# esp32.net
KiCad netlist of a schematic drawn in Altium Designer
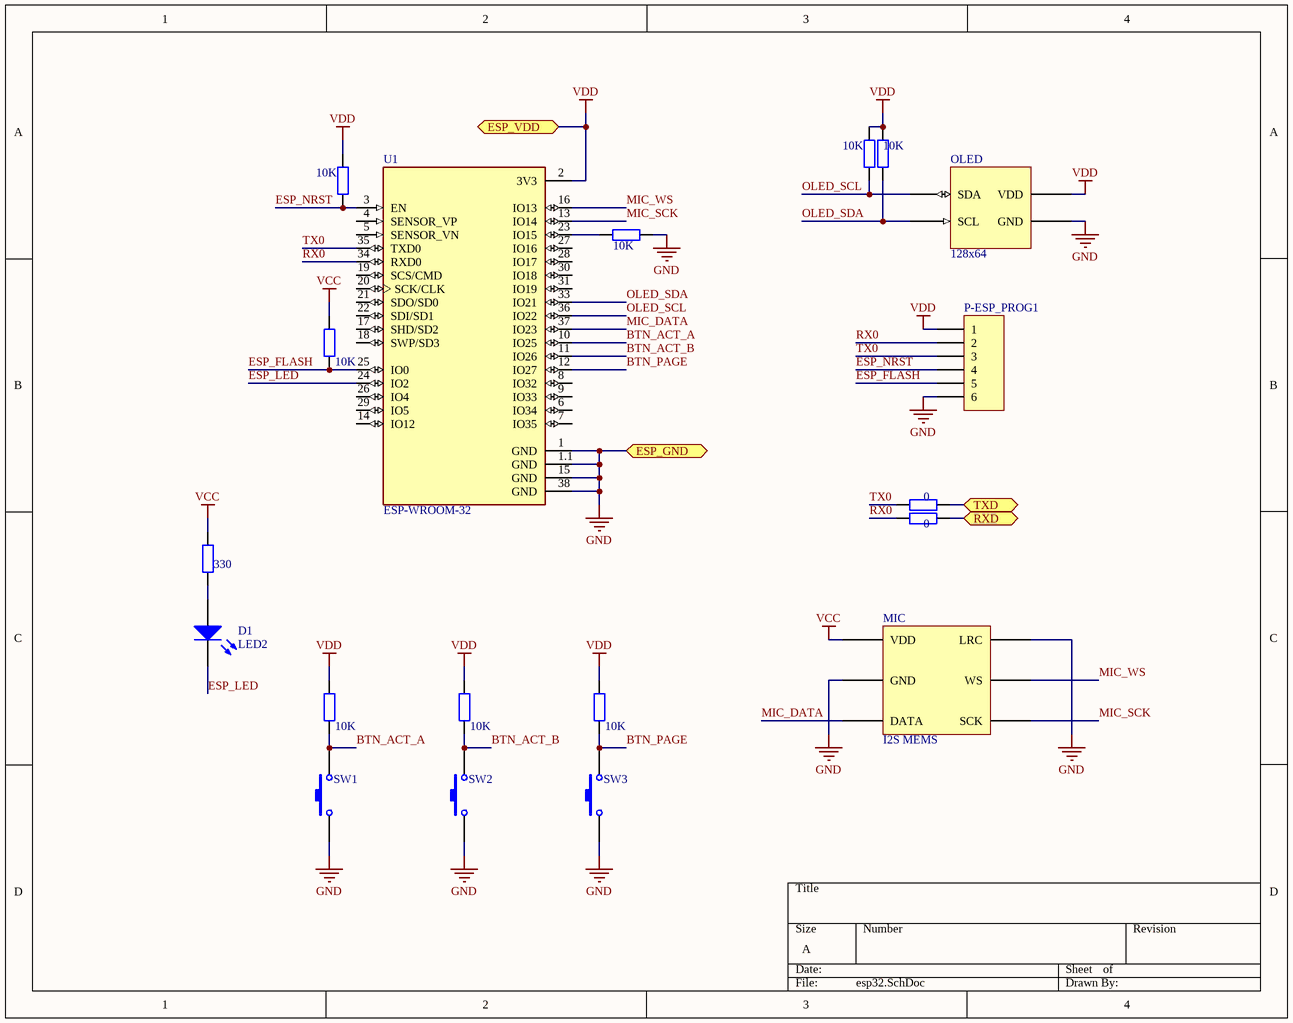
[diagram p0: esp32.SchDoc]

(export (version "E")
  (design (tool "Eeschema 10.0.6"))
  (components
    (comp (ref "D1")
      (value "LED2")
      (footprint "3.2X1.6X1.1")
      (description "Typical RED, GREEN, YELLOW, AMBER GaAs LED")
      (fields (field (name "PUBLISHER") "Altium Limited"))
      (libsource (lib "Miscellaneous Devices") (part "LED2"))
    )
    (comp (ref "MIC") (value "I2S MEMS") (libsource (lib "INMP441") (part "INMP441")))
    (comp (ref "OLED") (value "128x64") (libsource (lib "SH1106") (part "SH1106")))
    (comp (ref "P-ESP_PROG1")
      (value "Header 6")
      (footprint "HDR1X6")
      (description "Header, 6-Pin")
      (fields (field (name "PUBLISHER") "Altium Limited"))
      (libsource (lib "Miscellaneous Connectors") (part "Header 6"))
    )
    (comp (ref "R-BUTTON1")
      (value "10K")
      (footprint "AXIAL-0.4")
      (description "Resistor")
      (fields (field (name "Comment") "Res2") (field (name "PUBLISHER") "Altium Limited"))
      (libsource (lib "Miscellaneous Devices") (part "Res2"))
    )
    (comp (ref "R-BUTTON2")
      (value "10K")
      (footprint "AXIAL-0.4")
      (description "Resistor")
      (fields (field (name "Comment") "Res2") (field (name "PUBLISHER") "Altium Limited"))
      (libsource (lib "Miscellaneous Devices") (part "Res2"))
    )
    (comp (ref "R-BUTTON3")
      (value "10K")
      (footprint "AXIAL-0.4")
      (description "Resistor")
      (fields (field (name "Comment") "Res2") (field (name "PUBLISHER") "Altium Limited"))
      (libsource (lib "Miscellaneous Devices") (part "Res2"))
    )
    (comp (ref "R-ESP-LOG1")
      (value "10K")
      (footprint "AXIAL-0.4")
      (description "Resistor")
      (fields (field (name "Comment") "Res2") (field (name "PUBLISHER") "Altium Limited"))
      (libsource (lib "") (part "Res2_2"))
    )
    (comp (ref "R-ESP1")
      (value "10K")
      (footprint "AXIAL-0.4")
      (description "Resistor")
      (fields (field (name "Comment") "Res2") (field (name "PUBLISHER") "Altium Limited"))
      (libsource (lib "Miscellaneous Devices") (part "Res2"))
    )
    (comp (ref "R-ESP2")
      (value "10K")
      (footprint "AXIAL-0.4")
      (description "Resistor")
      (fields (field (name "Comment") "Res2") (field (name "PUBLISHER") "Altium Limited"))
      (libsource (lib "Miscellaneous Devices") (part "Res2"))
    )
    (comp (ref "R-LED1")
      (value "330")
      (footprint "AXIAL-0.4")
      (description "Resistor")
      (fields (field (name "Comment") "Res2") (field (name "PUBLISHER") "Altium Limited"))
      (libsource (lib "Miscellaneous Devices") (part "Res2"))
    )
    (comp (ref "R-OLED1")
      (value "10K")
      (footprint "AXIAL-0.4")
      (description "Resistor")
      (fields (field (name "Comment") "Res2") (field (name "PUBLISHER") "Altium Limited"))
      (libsource (lib "Miscellaneous Devices") (part "Res2"))
    )
    (comp (ref "R-OLED2")
      (value "10K")
      (footprint "AXIAL-0.4")
      (description "Resistor")
      (fields (field (name "Comment") "Res2") (field (name "PUBLISHER") "Altium Limited"))
      (libsource (lib "Miscellaneous Devices") (part "Res2"))
    )
    (comp (ref "R-UART1")
      (value "0")
      (footprint "AXIAL-0.4")
      (description "Resistor")
      (fields (field (name "Comment") "Res2") (field (name "PUBLISHER") "Altium Limited"))
      (libsource (lib "") (part "Res2_1"))
    )
    (comp (ref "R-UART2")
      (value "0")
      (footprint "AXIAL-0.4")
      (description "Resistor")
      (fields (field (name "Comment") "Res2") (field (name "PUBLISHER") "Altium Limited"))
      (libsource (lib "") (part "Res2_1"))
    )
    (comp (ref "SW1")
      (value "SW-PB")
      (footprint "SPST-2")
      (description "Switch")
      (fields (field (name "PUBLISHER") "Altium Limited"))
      (libsource (lib "Miscellaneous Devices") (part "SW-PB"))
    )
    (comp (ref "SW2")
      (value "SW-PB")
      (footprint "SPST-2")
      (description "Switch")
      (fields (field (name "PUBLISHER") "Altium Limited"))
      (libsource (lib "Miscellaneous Devices") (part "SW-PB"))
    )
    (comp (ref "SW3")
      (value "SW-PB")
      (footprint "SPST-2")
      (description "Switch")
      (fields (field (name "PUBLISHER") "Altium Limited"))
      (libsource (lib "Miscellaneous Devices") (part "SW-PB"))
    )
    (comp (ref "U1")
      (value "ESP-WROOM-32")
      (footprint "MODULE_ESP-WROOM-32")
      (description "WiFi 802.11b/g/n/d/e/i Transceiver Module 2.4GHz Surface Mount")
      (fields (field (name "MF") "Olimex LTD"))
      (libsource (lib "ESP-WROOM-32") (part "ESP-WROOM-32"))
    )
  )
  (nets
    (net (code "1") (name "/BTN_ACT_A") (class "Default")
      (node (ref "R-BUTTON1") (pin "1") (pinfunction "1_1") (pintype "passive"))
      (node (ref "SW1") (pin "2") (pinfunction "2_2") (pintype "passive"))
      (node (ref "U1") (pin "10") (pinfunction "IO25_10") (pintype "bidirectional"))
    )
    (net (code "2") (name "/BTN_ACT_B") (class "Default")
      (node (ref "R-BUTTON2") (pin "1") (pinfunction "1_1") (pintype "passive"))
      (node (ref "SW2") (pin "2") (pinfunction "2_2") (pintype "passive"))
      (node (ref "U1") (pin "11") (pinfunction "IO26_11") (pintype "bidirectional"))
    )
    (net (code "3") (name "/BTN_PAGE") (class "Default")
      (node (ref "R-BUTTON3") (pin "1") (pinfunction "1_1") (pintype "passive"))
      (node (ref "SW3") (pin "2") (pinfunction "2_2") (pintype "passive"))
      (node (ref "U1") (pin "12") (pinfunction "IO27_12") (pintype "bidirectional"))
    )
    (net (code "4") (name "/ESP_FLASH") (class "Default")
      (node (ref "P-ESP_PROG1") (pin "5") (pinfunction "5_5") (pintype "passive"))
      (node (ref "R-ESP2") (pin "1") (pinfunction "1_1") (pintype "passive"))
      (node (ref "U1") (pin "25") (pinfunction "IO0_25") (pintype "bidirectional"))
    )
    (net (code "5") (name "/ESP_LED") (class "Default")
      (node (ref "D1") (pin "2") (pinfunction "K_2") (pintype "passive"))
      (node (ref "U1") (pin "24") (pinfunction "IO2_24") (pintype "bidirectional"))
    )
    (net (code "6") (name "/ESP_NRST") (class "Default")
      (node (ref "P-ESP_PROG1") (pin "4") (pinfunction "4_4") (pintype "passive"))
      (node (ref "R-ESP1") (pin "1") (pinfunction "1_1") (pintype "passive"))
      (node (ref "U1") (pin "3") (pinfunction "EN_3") (pintype "input"))
    )
    (net (code "7") (name "/MIC_DATA") (class "Default")
      (node (ref "MIC") (pin "DATA") (pinfunction "DATA_DATA") (pintype "passive"))
      (node (ref "U1") (pin "37") (pinfunction "IO23_37") (pintype "bidirectional"))
    )
    (net (code "8") (name "/MIC_SCK") (class "Default")
      (node (ref "MIC") (pin "SCK") (pinfunction "SCK_SCK") (pintype "passive"))
      (node (ref "U1") (pin "13") (pinfunction "IO14_13") (pintype "bidirectional"))
    )
    (net (code "9") (name "/MIC_WS") (class "Default")
      (node (ref "MIC") (pin "WS") (pinfunction "WS_WS") (pintype "passive"))
      (node (ref "U1") (pin "16") (pinfunction "IO13_16") (pintype "bidirectional"))
    )
    (net (code "10") (name "/OLED_SCL") (class "Default")
      (node (ref "OLED") (pin "SDA") (pinfunction "SDA_SDA") (pintype "bidirectional"))
      (node (ref "R-OLED2") (pin "1") (pinfunction "1_1") (pintype "passive"))
      (node (ref "U1") (pin "36") (pinfunction "IO22_36") (pintype "bidirectional"))
    )
    (net (code "11") (name "/OLED_SDA") (class "Default")
      (node (ref "OLED") (pin "SCL") (pinfunction "SCL_SCL") (pintype "input"))
      (node (ref "R-OLED1") (pin "1") (pinfunction "1_1") (pintype "passive"))
      (node (ref "U1") (pin "33") (pinfunction "IO21_33") (pintype "bidirectional"))
    )
    (net (code "12") (name "/RX0") (class "Default")
      (node (ref "P-ESP_PROG1") (pin "2") (pinfunction "2_2") (pintype "passive"))
      (node (ref "R-UART2") (pin "1") (pinfunction "1_1") (pintype "passive"))
      (node (ref "U1") (pin "34") (pinfunction "RXD0_34") (pintype "bidirectional"))
    )
    (net (code "13") (name "/RXD") (class "Default")
      (node (ref "R-UART2") (pin "2") (pinfunction "2_2") (pintype "passive"))
    )
    (net (code "14") (name "/TX0") (class "Default")
      (node (ref "P-ESP_PROG1") (pin "3") (pinfunction "3_3") (pintype "passive"))
      (node (ref "R-UART1") (pin "1") (pinfunction "1_1") (pintype "passive"))
      (node (ref "U1") (pin "35") (pinfunction "TXD0_35") (pintype "bidirectional"))
    )
    (net (code "15") (name "/TXD") (class "Default")
      (node (ref "R-UART1") (pin "2") (pinfunction "2_2") (pintype "passive"))
    )
    (net (code "16") (name "GND") (class "Default")
      (node (ref "MIC") (pin "GND") (pinfunction "GND_GND") (pintype "power_in"))
      (node (ref "MIC") (pin "LRC") (pinfunction "LRC_LRC") (pintype "passive"))
      (node (ref "OLED") (pin "GND") (pinfunction "GND_GND") (pintype "power_in"))
      (node (ref "P-ESP_PROG1") (pin "6") (pinfunction "6_6") (pintype "passive"))
      (node (ref "R-ESP-LOG1") (pin "1") (pinfunction "1_1") (pintype "passive"))
      (node (ref "SW1") (pin "1") (pinfunction "1_1") (pintype "passive"))
      (node (ref "SW2") (pin "1") (pinfunction "1_1") (pintype "passive"))
      (node (ref "SW3") (pin "1") (pinfunction "1_1") (pintype "passive"))
      (node (ref "U1") (pin "1") (pinfunction "GND_1") (pintype "power_in"))
      (node (ref "U1") (pin "1.1") (pinfunction "GND_1.1") (pintype "power_in"))
      (node (ref "U1") (pin "15") (pinfunction "GND_15") (pintype "power_in"))
      (node (ref "U1") (pin "38") (pinfunction "GND_38") (pintype "power_in"))
    )
    (net (code "17") (name "Net-(D1-A)") (class "Default")
      (node (ref "D1") (pin "1") (pinfunction "A_1") (pintype "passive"))
      (node (ref "R-LED1") (pin "1") (pinfunction "1_1") (pintype "passive"))
    )
    (net (code "18") (name "Net-(U1-IO15)") (class "Default")
      (node (ref "R-ESP-LOG1") (pin "2") (pinfunction "2_2") (pintype "passive"))
      (node (ref "U1") (pin "23") (pinfunction "IO15_23") (pintype "bidirectional"))
    )
    (net (code "19") (name "VCC") (class "Default")
      (node (ref "MIC") (pin "VDD") (pinfunction "VDD_VDD") (pintype "power_in"))
      (node (ref "R-ESP2") (pin "2") (pinfunction "2_2") (pintype "passive"))
      (node (ref "R-LED1") (pin "2") (pinfunction "2_2") (pintype "passive"))
    )
    (net (code "20") (name "VDD") (class "Default")
      (node (ref "OLED") (pin "VDD") (pinfunction "VDD_VDD") (pintype "power_in"))
      (node (ref "P-ESP_PROG1") (pin "1") (pinfunction "1_1") (pintype "passive"))
      (node (ref "R-BUTTON1") (pin "2") (pinfunction "2_2") (pintype "passive"))
      (node (ref "R-BUTTON2") (pin "2") (pinfunction "2_2") (pintype "passive"))
      (node (ref "R-BUTTON3") (pin "2") (pinfunction "2_2") (pintype "passive"))
      (node (ref "R-ESP1") (pin "2") (pinfunction "2_2") (pintype "passive"))
      (node (ref "R-OLED1") (pin "2") (pinfunction "2_2") (pintype "passive"))
      (node (ref "R-OLED2") (pin "2") (pinfunction "2_2") (pintype "passive"))
      (node (ref "U1") (pin "2") (pinfunction "3V3_2") (pintype "power_in"))
    )
    (net (code "21") (name "unconnected-(U1-IO4-Pad26)") (class "Default")
      (node (ref "U1") (pin "26") (pinfunction "IO4_26") (pintype "bidirectional"))
    )
    (net (code "22") (name "unconnected-(U1-IO5-Pad29)") (class "Default")
      (node (ref "U1") (pin "29") (pinfunction "IO5_29") (pintype "bidirectional"))
    )
    (net (code "23") (name "unconnected-(U1-IO12-Pad14)") (class "Default")
      (node (ref "U1") (pin "14") (pinfunction "IO12_14") (pintype "bidirectional"))
    )
    (net (code "24") (name "unconnected-(U1-IO16-Pad27)") (class "Default")
      (node (ref "U1") (pin "27") (pinfunction "IO16_27") (pintype "bidirectional"))
    )
    (net (code "25") (name "unconnected-(U1-IO17-Pad28)") (class "Default")
      (node (ref "U1") (pin "28") (pinfunction "IO17_28") (pintype "bidirectional"))
    )
    (net (code "26") (name "unconnected-(U1-IO18-Pad30)") (class "Default")
      (node (ref "U1") (pin "30") (pinfunction "IO18_30") (pintype "bidirectional"))
    )
    (net (code "27") (name "unconnected-(U1-IO19-Pad31)") (class "Default")
      (node (ref "U1") (pin "31") (pinfunction "IO19_31") (pintype "bidirectional"))
    )
    (net (code "28") (name "unconnected-(U1-IO32-Pad8)") (class "Default")
      (node (ref "U1") (pin "8") (pinfunction "IO32_8") (pintype "bidirectional"))
    )
    (net (code "29") (name "unconnected-(U1-IO33-Pad9)") (class "Default")
      (node (ref "U1") (pin "9") (pinfunction "IO33_9") (pintype "bidirectional"))
    )
    (net (code "30") (name "unconnected-(U1-IO34-Pad6)") (class "Default")
      (node (ref "U1") (pin "6") (pinfunction "IO34_6") (pintype "bidirectional"))
    )
    (net (code "31") (name "unconnected-(U1-IO35-Pad7)") (class "Default")
      (node (ref "U1") (pin "7") (pinfunction "IO35_7") (pintype "bidirectional"))
    )
    (net (code "32") (name "unconnected-(U1-SCK{slash}CLK-Pad20)") (class "Default")
      (node (ref "U1") (pin "20") (pinfunction "SCK/CLK_20") (pintype "bidirectional"))
    )
    (net (code "33") (name "unconnected-(U1-SCS{slash}CMD-Pad19)") (class "Default")
      (node (ref "U1") (pin "19") (pinfunction "SCS/CMD_19") (pintype "bidirectional"))
    )
    (net (code "34") (name "unconnected-(U1-SDI{slash}SD1-Pad22)") (class "Default")
      (node (ref "U1") (pin "22") (pinfunction "SDI/SD1_22") (pintype "bidirectional"))
    )
    (net (code "35") (name "unconnected-(U1-SDO{slash}SD0-Pad21)") (class "Default")
      (node (ref "U1") (pin "21") (pinfunction "SDO/SD0_21") (pintype "bidirectional"))
    )
    (net (code "36") (name "unconnected-(U1-SENSOR_VN-Pad5)") (class "Default")
      (node (ref "U1") (pin "5") (pinfunction "SENSOR_VN_5") (pintype "input"))
    )
    (net (code "37") (name "unconnected-(U1-SENSOR_VP-Pad4)") (class "Default")
      (node (ref "U1") (pin "4") (pinfunction "SENSOR_VP_4") (pintype "input"))
    )
    (net (code "38") (name "unconnected-(U1-SHD{slash}SD2-Pad17)") (class "Default")
      (node (ref "U1") (pin "17") (pinfunction "SHD/SD2_17") (pintype "bidirectional"))
    )
    (net (code "39") (name "unconnected-(U1-SWP{slash}SD3-Pad18)") (class "Default")
      (node (ref "U1") (pin "18") (pinfunction "SWP/SD3_18") (pintype "bidirectional"))
    )
  )
)
